# MUX.net
KiCad netlist of a schematic drawn in Altium Designer
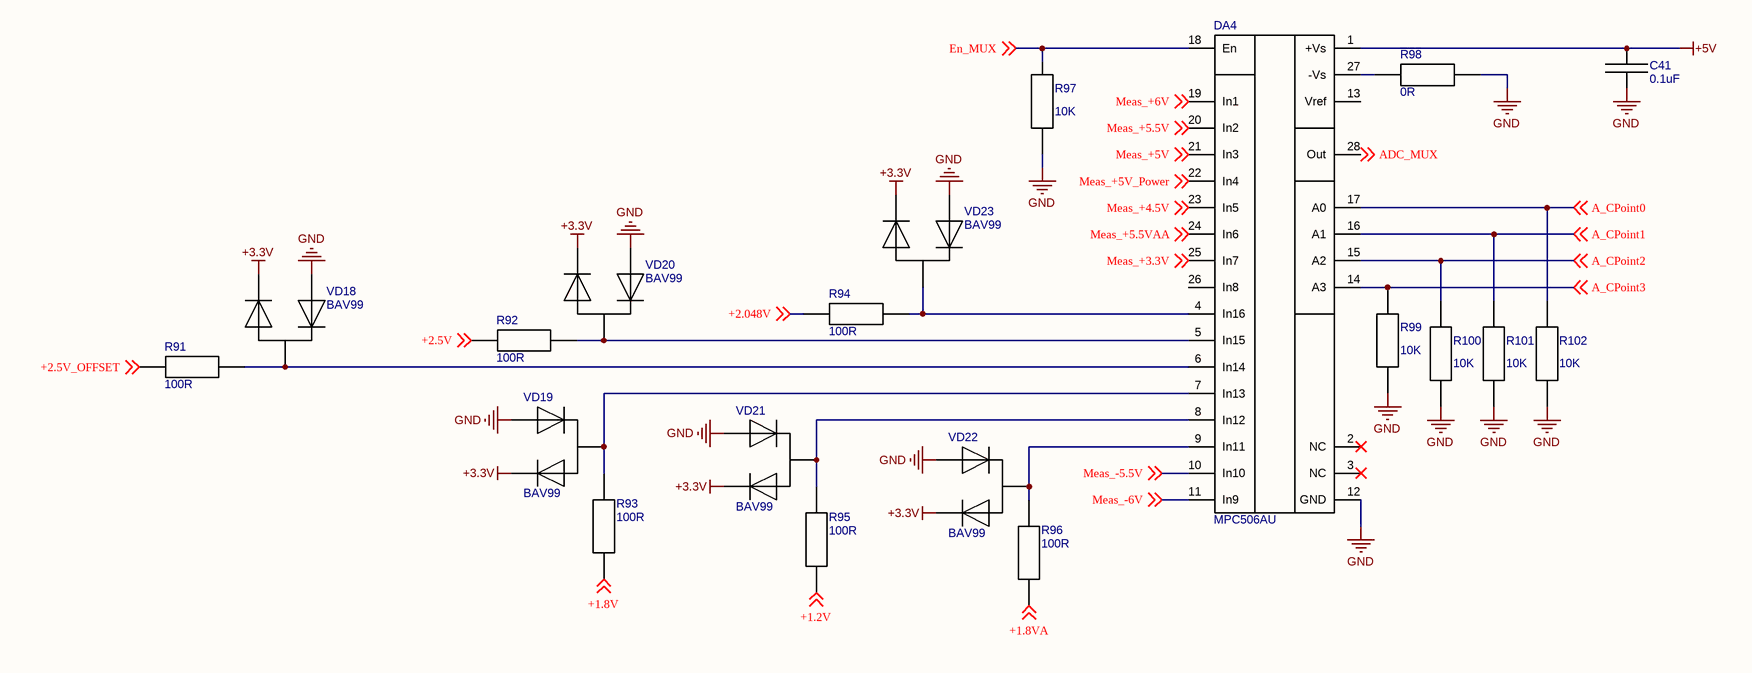
[diagram p0: MUX.SchDoc]

(export (version "E")
  (design (tool "Eeschema 10.0.6"))
  (components
    (comp (ref "C41")
      (value "0.1uF")
      (footprint "0603C")
      (description "C0603 0.1UF 10% 50V")
      (fields
        (field (name "PART NUMBER") "SMD CAP CER 0.1UF ±10% 50V X7R 0603")
        (field (name "ADDED_BY") "anton@teslatec.ru")
      )
      (libsource (lib "Test_Stand_Pergam") (part "C0603-0.1UF 10% 50V"))
    )
    (comp (ref "DA4")
      (value "MPC506AU")
      (footprint "SOIC-28")
      (description "MPC506AU, Ch: 16, SO28")
      (fields (field (name "PART NUMBER") "MPC506A") (field (name "ADDED_BY") "irdolgopolowa@yandex.ru"))
      (libsource (lib "Test_Stand_Pergam") (part "MPC506AU"))
    )
    (comp (ref "R91")
      (value "100R")
      (footprint "R0402")
      (description "Resistor SMD 100R 1% 0402")
      (fields
        (field (name "PART NUMBER") "SMD RES 100 OHM 1% ±100ppm/°C 0402")
        (field (name "ADDED_BY") "irdolgopolowa@yandex.ru")
      )
      (libsource (lib "Test_Stand_Pergam") (part "R0402-100R"))
    )
    (comp (ref "R92")
      (value "100R")
      (footprint "R0402")
      (description "Resistor SMD 100R 1% 0402")
      (fields
        (field (name "PART NUMBER") "SMD RES 100 OHM 1% ±100ppm/°C 0402")
        (field (name "ADDED_BY") "irdolgopolowa@yandex.ru")
      )
      (libsource (lib "Test_Stand_Pergam") (part "R0402-100R"))
    )
    (comp (ref "R93")
      (value "100R")
      (footprint "R0402")
      (description "Resistor SMD 100R 1% 0402")
      (fields
        (field (name "PART NUMBER") "SMD RES 100 OHM 1% ±100ppm/°C 0402")
        (field (name "ADDED_BY") "irdolgopolowa@yandex.ru")
      )
      (libsource (lib "Test_Stand_Pergam") (part "R0402-100R"))
    )
    (comp (ref "R94")
      (value "100R")
      (footprint "R0402")
      (description "Resistor SMD 100R 1% 0402")
      (fields
        (field (name "PART NUMBER") "SMD RES 100 OHM 1% ±100ppm/°C 0402")
        (field (name "ADDED_BY") "irdolgopolowa@yandex.ru")
      )
      (libsource (lib "Test_Stand_Pergam") (part "R0402-100R"))
    )
    (comp (ref "R95")
      (value "100R")
      (footprint "R0402")
      (description "Resistor SMD 100R 1% 0402")
      (fields
        (field (name "PART NUMBER") "SMD RES 100 OHM 1% ±100ppm/°C 0402")
        (field (name "ADDED_BY") "irdolgopolowa@yandex.ru")
      )
      (libsource (lib "Test_Stand_Pergam") (part "R0402-100R"))
    )
    (comp (ref "R96")
      (value "100R")
      (footprint "R0402")
      (description "Resistor SMD 100R 1% 0402")
      (fields
        (field (name "PART NUMBER") "SMD RES 100 OHM 1% ±100ppm/°C 0402")
        (field (name "ADDED_BY") "irdolgopolowa@yandex.ru")
      )
      (libsource (lib "Test_Stand_Pergam") (part "R0402-100R"))
    )
    (comp (ref "R97")
      (value "10K")
      (footprint "R0402")
      (description "Resistor SMD 10K 1% 0402")
      (fields
        (field (name "PART NUMBER") "SMD RES 10 KOHM 1% ±100ppm/°C 0402")
        (field (name "ADDED_BY") "Rutel@teslatec.ru")
      )
      (libsource (lib "Test_Stand_Pergam") (part "R0402-10K"))
    )
    (comp (ref "R98")
      (value "0R")
      (footprint "R0402")
      (description "Resistor SMD 0R 1% 0402")
      (fields
        (field (name "PART NUMBER") "SMD RES 0R 0402")
        (field (name "ADDED_BY") "irdolgopolowa@yandex.ru")
      )
      (libsource (lib "Test_Stand_Pergam") (part "R0402-0R"))
    )
    (comp (ref "R99")
      (value "10K")
      (footprint "R0402")
      (description "Resistor SMD 10K 1% 0402")
      (fields
        (field (name "PART NUMBER") "SMD RES 10 KOHM 1% ±100ppm/°C 0402")
        (field (name "ADDED_BY") "Rutel@teslatec.ru")
      )
      (libsource (lib "Test_Stand_Pergam") (part "R0402-10K"))
    )
    (comp (ref "R100")
      (value "10K")
      (footprint "R0402")
      (description "Resistor SMD 10K 1% 0402")
      (fields
        (field (name "PART NUMBER") "SMD RES 10 KOHM 1% ±100ppm/°C 0402")
        (field (name "ADDED_BY") "Rutel@teslatec.ru")
      )
      (libsource (lib "Test_Stand_Pergam") (part "R0402-10K"))
    )
    (comp (ref "R101")
      (value "10K")
      (footprint "R0402")
      (description "Resistor SMD 10K 1% 0402")
      (fields
        (field (name "PART NUMBER") "SMD RES 10 KOHM 1% ±100ppm/°C 0402")
        (field (name "ADDED_BY") "Rutel@teslatec.ru")
      )
      (libsource (lib "Test_Stand_Pergam") (part "R0402-10K"))
    )
    (comp (ref "R102")
      (value "10K")
      (footprint "R0402")
      (description "Resistor SMD 10K 1% 0402")
      (fields
        (field (name "PART NUMBER") "SMD RES 10 KOHM 1% ±100ppm/°C 0402")
        (field (name "ADDED_BY") "Rutel@teslatec.ru")
      )
      (libsource (lib "Test_Stand_Pergam") (part "R0402-10K"))
    )
    (comp (ref "VD18")
      (value "BAV99")
      (footprint "SOT-23-3")
      (description "BAV99, UMW, 70В, 200мА")
      (fields (field (name "ADDED_BY") "andrew@teslatec.ru"))
      (libsource (lib "Test_Stand_Pergam") (part "BAV99"))
    )
    (comp (ref "VD19")
      (value "BAV99")
      (footprint "SOT-23-3")
      (description "BAV99, UMW, 70В, 200мА")
      (fields (field (name "ADDED_BY") "andrew@teslatec.ru"))
      (libsource (lib "Test_Stand_Pergam") (part "BAV99"))
    )
    (comp (ref "VD20")
      (value "BAV99")
      (footprint "SOT-23-3")
      (description "BAV99, UMW, 70В, 200мА")
      (fields (field (name "ADDED_BY") "andrew@teslatec.ru"))
      (libsource (lib "Test_Stand_Pergam") (part "BAV99"))
    )
    (comp (ref "VD21")
      (value "BAV99")
      (footprint "SOT-23-3")
      (description "BAV99, UMW, 70В, 200мА")
      (fields (field (name "ADDED_BY") "andrew@teslatec.ru"))
      (libsource (lib "Test_Stand_Pergam") (part "BAV99"))
    )
    (comp (ref "VD22")
      (value "BAV99")
      (footprint "SOT-23-3")
      (description "BAV99, UMW, 70В, 200мА")
      (fields (field (name "ADDED_BY") "andrew@teslatec.ru"))
      (libsource (lib "Test_Stand_Pergam") (part "BAV99"))
    )
    (comp (ref "VD23")
      (value "BAV99")
      (footprint "SOT-23-3")
      (description "BAV99, UMW, 70В, 200мА")
      (fields (field (name "ADDED_BY") "andrew@teslatec.ru"))
      (libsource (lib "Test_Stand_Pergam") (part "BAV99"))
    )
  )
  (nets
    (net (code "1") (name "+1.2V") (class "Default")
      (node (ref "R95") (pin "1") (pinfunction "1_1") (pintype "passive"))
    )
    (net (code "2") (name "+1.8V") (class "Default")
      (node (ref "R93") (pin "1") (pinfunction "1_1") (pintype "passive"))
    )
    (net (code "3") (name "+1.8VA") (class "Default")
      (node (ref "R96") (pin "1") (pinfunction "1_1") (pintype "passive"))
    )
    (net (code "4") (name "+2.5V") (class "Default")
      (node (ref "R92") (pin "1") (pinfunction "1_1") (pintype "passive"))
    )
    (net (code "5") (name "+2.5V_OFFSET") (class "Default")
      (node (ref "R91") (pin "1") (pinfunction "1_1") (pintype "passive"))
    )
    (net (code "6") (name "+2.048V") (class "Default")
      (node (ref "R94") (pin "1") (pinfunction "1_1") (pintype "passive"))
    )
    (net (code "7") (name "+3.3V") (class "Default")
      (node (ref "VD18") (pin "2") (pinfunction "2_2") (pintype "passive"))
      (node (ref "VD19") (pin "2") (pinfunction "2_2") (pintype "passive"))
      (node (ref "VD20") (pin "2") (pinfunction "2_2") (pintype "passive"))
      (node (ref "VD21") (pin "2") (pinfunction "2_2") (pintype "passive"))
      (node (ref "VD22") (pin "2") (pinfunction "2_2") (pintype "passive"))
      (node (ref "VD23") (pin "2") (pinfunction "2_2") (pintype "passive"))
    )
    (net (code "8") (name "+5V") (class "Default")
      (node (ref "C41") (pin "1") (pinfunction "1_1") (pintype "passive"))
      (node (ref "DA4") (pin "1") (pinfunction "+Vs_1") (pintype "passive"))
    )
    (net (code "9") (name "ADC_MUX") (class "Default")
      (node (ref "DA4") (pin "28") (pinfunction "Out_28") (pintype "passive"))
    )
    (net (code "10") (name "A_CPoint0") (class "Default")
      (node (ref "DA4") (pin "17") (pinfunction "A0_17") (pintype "passive"))
      (node (ref "R102") (pin "2") (pinfunction "2_2") (pintype "passive"))
    )
    (net (code "11") (name "A_CPoint1") (class "Default")
      (node (ref "DA4") (pin "16") (pinfunction "A1_16") (pintype "passive"))
      (node (ref "R101") (pin "2") (pinfunction "2_2") (pintype "passive"))
    )
    (net (code "12") (name "A_CPoint2") (class "Default")
      (node (ref "DA4") (pin "15") (pinfunction "A2_15") (pintype "passive"))
      (node (ref "R100") (pin "2") (pinfunction "2_2") (pintype "passive"))
    )
    (net (code "13") (name "A_CPoint3") (class "Default")
      (node (ref "DA4") (pin "14") (pinfunction "A3_14") (pintype "passive"))
      (node (ref "R99") (pin "2") (pinfunction "2_2") (pintype "passive"))
    )
    (net (code "14") (name "En_MUX") (class "Default")
      (node (ref "DA4") (pin "18") (pinfunction "En_18") (pintype "passive"))
      (node (ref "R97") (pin "1") (pinfunction "1_1") (pintype "passive"))
    )
    (net (code "15") (name "GND") (class "Default")
      (node (ref "C41") (pin "2") (pinfunction "2_2") (pintype "passive"))
      (node (ref "DA4") (pin "12") (pinfunction "GND_12") (pintype "passive"))
      (node (ref "R100") (pin "1") (pinfunction "1_1") (pintype "passive"))
      (node (ref "R101") (pin "1") (pinfunction "1_1") (pintype "passive"))
      (node (ref "R102") (pin "1") (pinfunction "1_1") (pintype "passive"))
      (node (ref "R97") (pin "2") (pinfunction "2_2") (pintype "passive"))
      (node (ref "R98") (pin "1") (pinfunction "1_1") (pintype "passive"))
      (node (ref "R99") (pin "1") (pinfunction "1_1") (pintype "passive"))
      (node (ref "VD18") (pin "1") (pinfunction "1_1") (pintype "passive"))
      (node (ref "VD19") (pin "1") (pinfunction "1_1") (pintype "passive"))
      (node (ref "VD20") (pin "1") (pinfunction "1_1") (pintype "passive"))
      (node (ref "VD21") (pin "1") (pinfunction "1_1") (pintype "passive"))
      (node (ref "VD22") (pin "1") (pinfunction "1_1") (pintype "passive"))
      (node (ref "VD23") (pin "1") (pinfunction "1_1") (pintype "passive"))
    )
    (net (code "16") (name "Meas_+3.3V") (class "Default")
      (node (ref "DA4") (pin "25") (pinfunction "In7_25") (pintype "passive"))
    )
    (net (code "17") (name "Meas_+4.5V") (class "Default")
      (node (ref "DA4") (pin "23") (pinfunction "In5_23") (pintype "passive"))
    )
    (net (code "18") (name "Meas_+5.5V") (class "Default")
      (node (ref "DA4") (pin "20") (pinfunction "In2_20") (pintype "passive"))
    )
    (net (code "19") (name "Meas_+5.5VAA") (class "Default")
      (node (ref "DA4") (pin "24") (pinfunction "In6_24") (pintype "passive"))
    )
    (net (code "20") (name "Meas_+5V") (class "Default")
      (node (ref "DA4") (pin "21") (pinfunction "In3_21") (pintype "passive"))
    )
    (net (code "21") (name "Meas_+5V_Power") (class "Default")
      (node (ref "DA4") (pin "22") (pinfunction "In4_22") (pintype "passive"))
    )
    (net (code "22") (name "Meas_+6V") (class "Default")
      (node (ref "DA4") (pin "19") (pinfunction "In1_19") (pintype "passive"))
    )
    (net (code "23") (name "Meas_-5.5V") (class "Default")
      (node (ref "DA4") (pin "10") (pinfunction "In10_10") (pintype "passive"))
    )
    (net (code "24") (name "Meas_-6V") (class "Default")
      (node (ref "DA4") (pin "11") (pinfunction "In9_11") (pintype "passive"))
    )
    (net (code "25") (name "Net-(DA4--Vs)") (class "Default")
      (node (ref "DA4") (pin "27") (pinfunction "-Vs_27") (pintype "passive"))
      (node (ref "R98") (pin "2") (pinfunction "2_2") (pintype "passive"))
    )
    (net (code "26") (name "Net-(DA4-In11)") (class "Default")
      (node (ref "DA4") (pin "9") (pinfunction "In11_9") (pintype "passive"))
      (node (ref "R96") (pin "2") (pinfunction "2_2") (pintype "passive"))
      (node (ref "VD22") (pin "3") (pinfunction "3_3") (pintype "passive"))
    )
    (net (code "27") (name "Net-(DA4-In12)") (class "Default")
      (node (ref "DA4") (pin "8") (pinfunction "In12_8") (pintype "passive"))
      (node (ref "R95") (pin "2") (pinfunction "2_2") (pintype "passive"))
      (node (ref "VD21") (pin "3") (pinfunction "3_3") (pintype "passive"))
    )
    (net (code "28") (name "Net-(DA4-In13)") (class "Default")
      (node (ref "DA4") (pin "7") (pinfunction "In13_7") (pintype "passive"))
      (node (ref "R93") (pin "2") (pinfunction "2_2") (pintype "passive"))
      (node (ref "VD19") (pin "3") (pinfunction "3_3") (pintype "passive"))
    )
    (net (code "29") (name "Net-(DA4-In14)") (class "Default")
      (node (ref "DA4") (pin "6") (pinfunction "In14_6") (pintype "passive"))
      (node (ref "R91") (pin "2") (pinfunction "2_2") (pintype "passive"))
      (node (ref "VD18") (pin "3") (pinfunction "3_3") (pintype "passive"))
    )
    (net (code "30") (name "Net-(DA4-In15)") (class "Default")
      (node (ref "DA4") (pin "5") (pinfunction "In15_5") (pintype "passive"))
      (node (ref "R92") (pin "2") (pinfunction "2_2") (pintype "passive"))
      (node (ref "VD20") (pin "3") (pinfunction "3_3") (pintype "passive"))
    )
    (net (code "31") (name "Net-(DA4-In16)") (class "Default")
      (node (ref "DA4") (pin "4") (pinfunction "In16_4") (pintype "passive"))
      (node (ref "R94") (pin "2") (pinfunction "2_2") (pintype "passive"))
      (node (ref "VD23") (pin "3") (pinfunction "3_3") (pintype "passive"))
    )
    (net (code "32") (name "unconnected-(DA4-In8-Pad26)") (class "Default")
      (node (ref "DA4") (pin "26") (pinfunction "In8_26") (pintype "passive"))
    )
    (net (code "33") (name "unconnected-(DA4-NC-Pad2)") (class "Default")
      (node (ref "DA4") (pin "2") (pinfunction "NC_2") (pintype "passive+no_connect"))
    )
    (net (code "34") (name "unconnected-(DA4-NC-Pad3)") (class "Default")
      (node (ref "DA4") (pin "3") (pinfunction "NC_3") (pintype "passive+no_connect"))
    )
    (net (code "35") (name "unconnected-(DA4-Vref-Pad13)") (class "Default")
      (node (ref "DA4") (pin "13") (pinfunction "Vref_13") (pintype "passive"))
    )
  )
)
